# ws2812b.net
KiCad netlist of a schematic drawn in Altium Designer
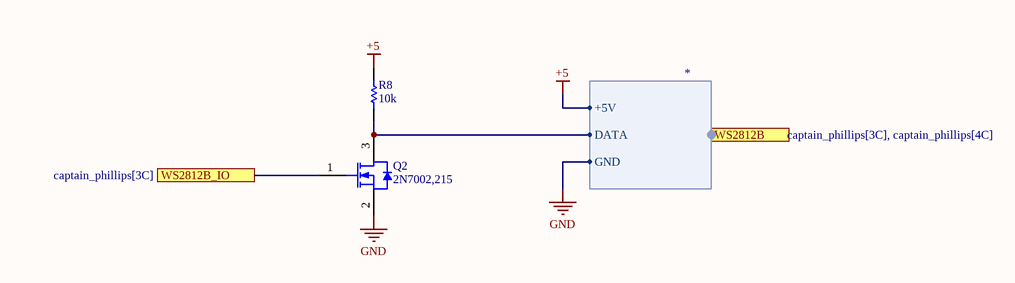
[diagram p0: ws2812b.SchDoc]

(export (version "E")
  (design (tool "Eeschema 10.0.6"))
  (components
    (comp (ref "Q2")
      (value "2N7002,215")
      (footprint "NXP-SOT23-3_V")
      (fields
        (field (name "POWER") "830mW")
        (field (name "LCSC PART NUMBER") "C8545")
        (field (name "MANUFACTURER") "NXP Semiconductors")
      )
      (libsource (lib "Dalhousie Formula SAE") (part "NEMOS-GSD-3"))
    )
    (comp (ref "R8")
      (value "10k")
      (footprint "RESC1608X55X25ML10T15")
      (description "0603 (1608 Metric) 1/10 W 10K 1 Thick Film Chip Resistor")
      (fields (field (name "POWER") "100mW") (field (name "LCSC PART NUMBER") "C25804"))
      (libsource (lib "Dalhousie Formula SAE") (part "RES-2"))
    )
  )
  (nets
    (net (code "2") (name "+5") (class "Default")
      (node (ref "R8") (pin "2") (pinfunction "2_2") (pintype "passive"))
    )
    (net (code "3") (name "/WS2812B_IO") (class "Default")
      (node (ref "Q2") (pin "1") (pinfunction "G_1") (pintype "passive"))
    )
    (net (code "5") (name "GND") (class "Default")
      (node (ref "Q2") (pin "2") (pinfunction "S_2") (pintype "passive"))
    )
    (net (code "6") (name "Net-(Q2-D)") (class "Default")
      (node (ref "Q2") (pin "3") (pinfunction "D_3") (pintype "passive"))
      (node (ref "R8") (pin "1") (pinfunction "1_1") (pintype "passive"))
    )
  )
)
